# uCopter.net
KiCad netlist of a schematic drawn in EAGLE
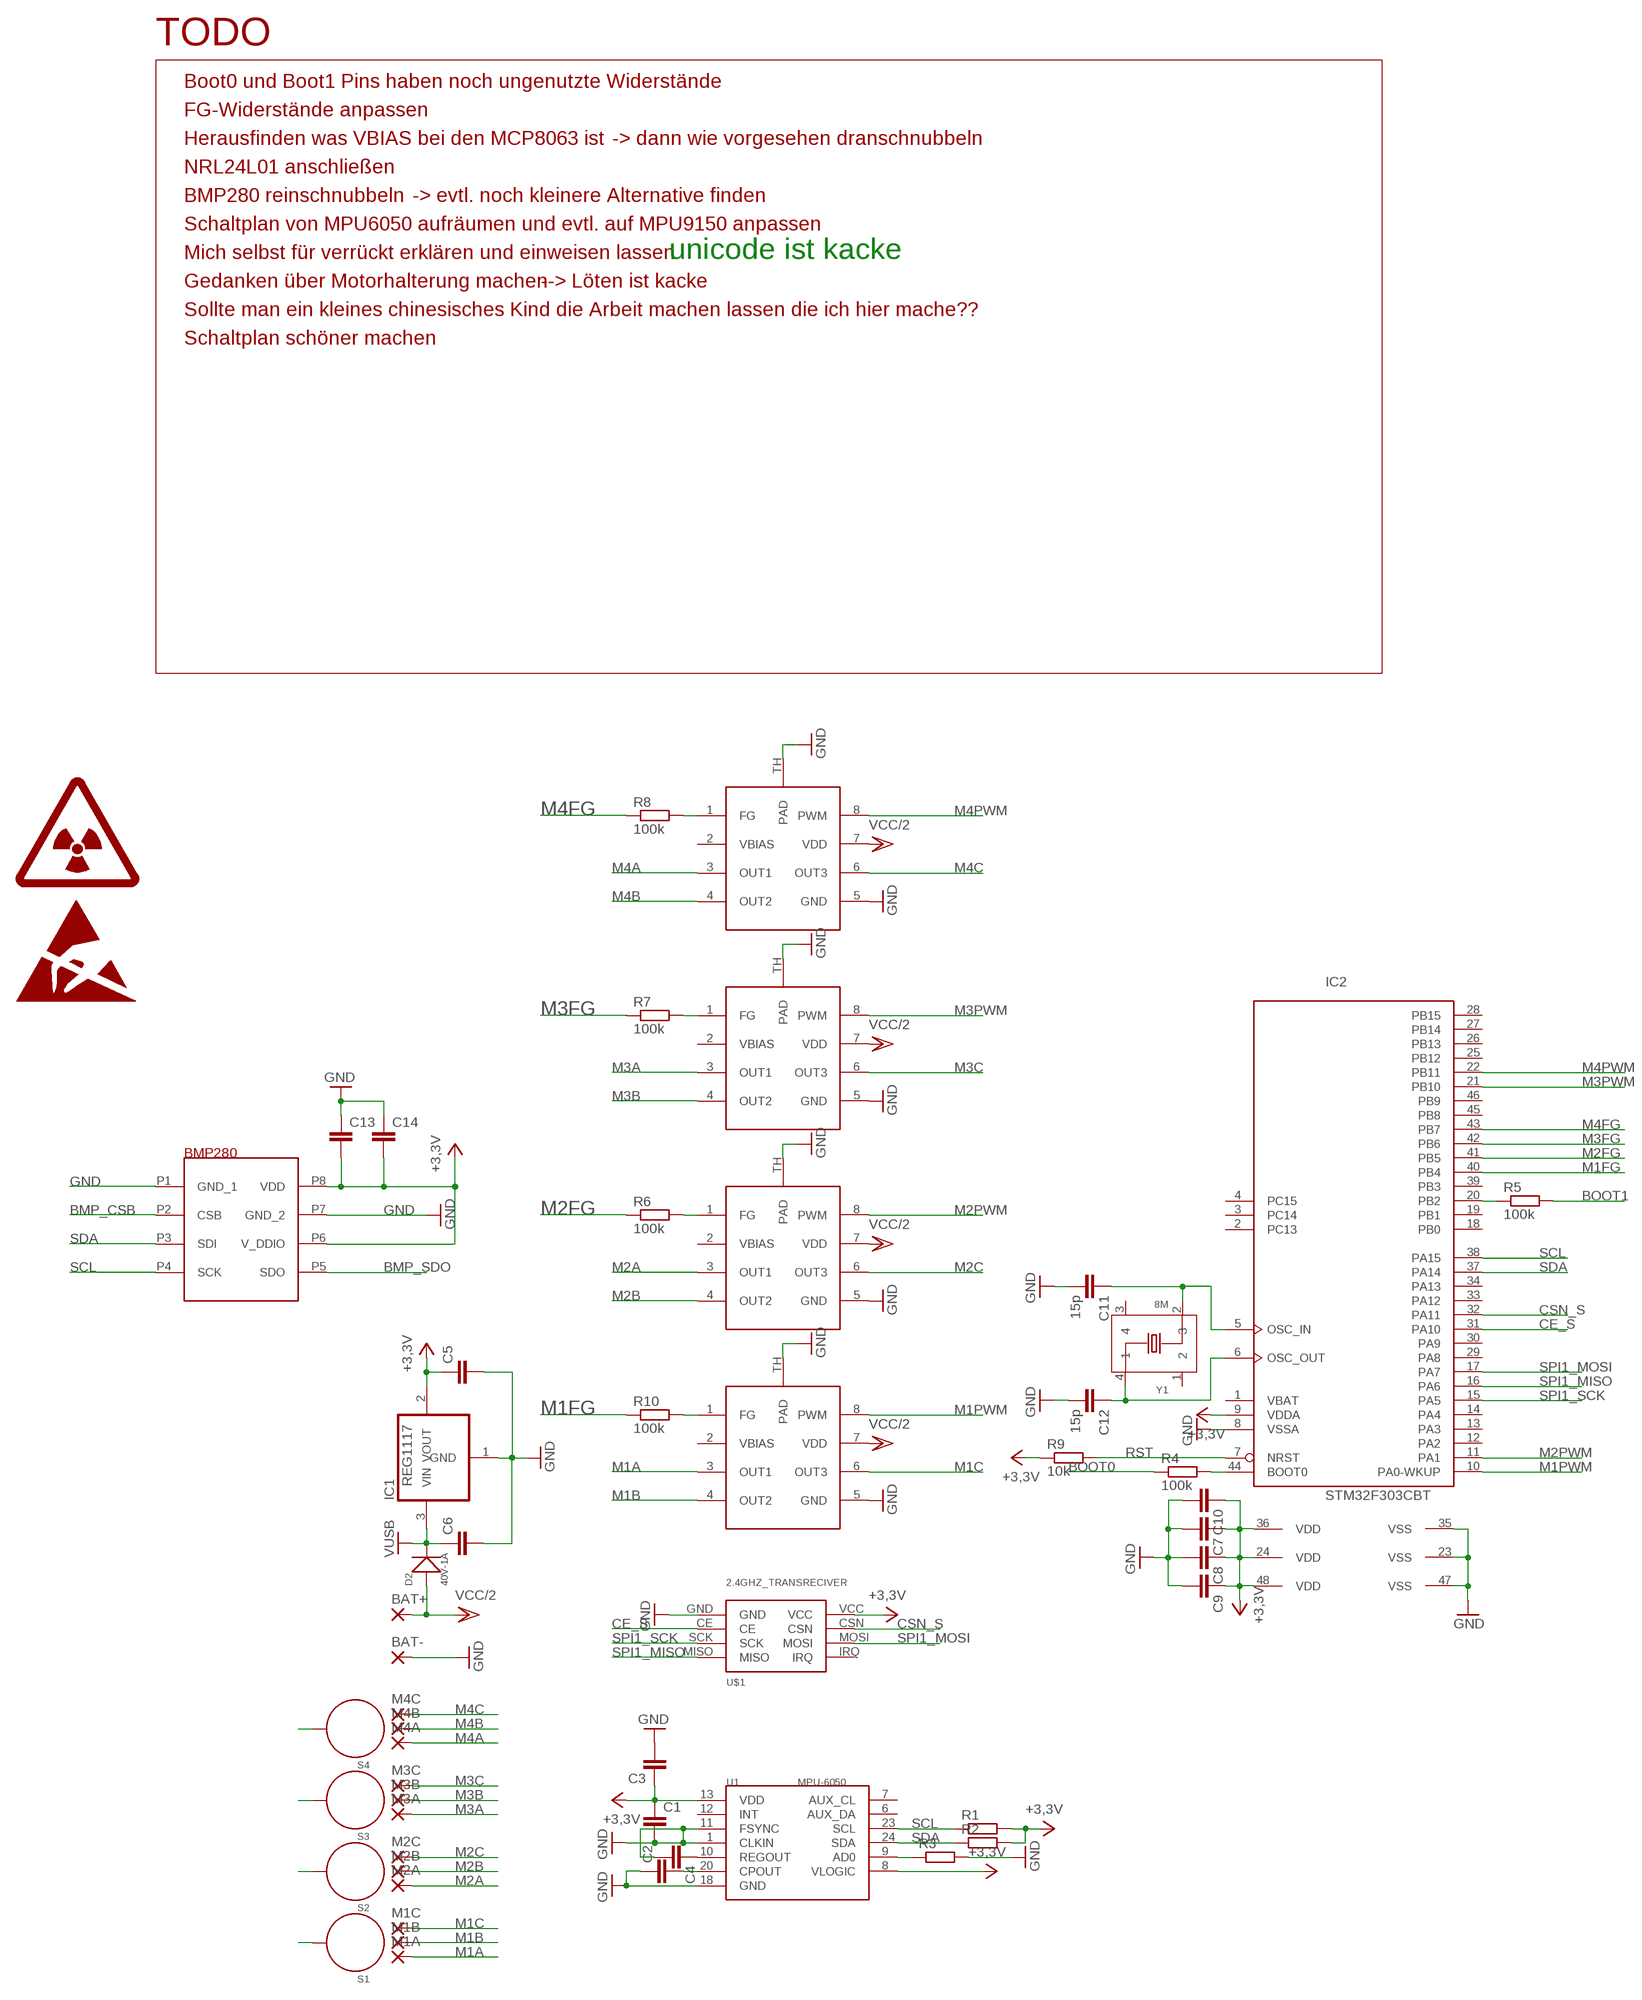
[diagram p0: schematic, sheet 1]

(export (version "E")
  (design (tool "Eeschema 10.0.6"))
  (components
    (comp (ref "BAT+")
      (value "SMD2")
      (footprint "eagle-import:SMD1,27-2,54")
      (libsource (lib "eagle-import") (part "SMD2"))
    )
    (comp (ref "BAT-")
      (value "SMD2")
      (footprint "eagle-import:SMD1,27-2,54")
      (libsource (lib "eagle-import") (part "SMD2"))
    )
    (comp (ref "C1")
      (value "C-EUC0402")
      (footprint "eagle-import:C0402")
      (libsource (lib "eagle-import") (part "C-EUC0402"))
    )
    (comp (ref "C2")
      (value "C-EUC0402")
      (footprint "eagle-import:C0402")
      (libsource (lib "eagle-import") (part "C-EUC0402"))
    )
    (comp (ref "C3")
      (value "C-EUC0402")
      (footprint "eagle-import:C0402")
      (libsource (lib "eagle-import") (part "C-EUC0402"))
    )
    (comp (ref "C4")
      (value "C-EUC0402")
      (footprint "eagle-import:C0402")
      (libsource (lib "eagle-import") (part "C-EUC0402"))
    )
    (comp (ref "C5")
      (value "C-EUC0603")
      (footprint "eagle-import:C0603")
      (libsource (lib "eagle-import") (part "C-EUC0603"))
    )
    (comp (ref "C6")
      (value "C-EUC0603")
      (footprint "eagle-import:C0603")
      (libsource (lib "eagle-import") (part "C-EUC0603"))
    )
    (comp (ref "C7")
      (value "C-EUC0402")
      (footprint "eagle-import:C0402")
      (libsource (lib "eagle-import") (part "C-EUC0402"))
    )
    (comp (ref "C8")
      (value "C-EUC0402")
      (footprint "eagle-import:C0402")
      (libsource (lib "eagle-import") (part "C-EUC0402"))
    )
    (comp (ref "C9")
      (value "C-EUC0402")
      (footprint "eagle-import:C0402")
      (libsource (lib "eagle-import") (part "C-EUC0402"))
    )
    (comp (ref "C10")
      (value "C-EUC0402")
      (footprint "eagle-import:C0402")
      (libsource (lib "eagle-import") (part "C-EUC0402"))
    )
    (comp (ref "C11")
      (value "15p")
      (footprint "eagle-import:C0402")
      (libsource (lib "eagle-import") (part "C-EUC0402"))
    )
    (comp (ref "C12")
      (value "15p")
      (footprint "eagle-import:C0402")
      (libsource (lib "eagle-import") (part "C-EUC0402"))
    )
    (comp (ref "C13")
      (value "C-EUC0402")
      (footprint "eagle-import:C0402")
      (libsource (lib "eagle-import") (part "C-EUC0402"))
    )
    (comp (ref "C14")
      (value "C-EUC0402")
      (footprint "eagle-import:C0402")
      (libsource (lib "eagle-import") (part "C-EUC0402"))
    )
    (comp (ref "D2")
      (value "40V-1A")
      (footprint "eagle-import:DO-214AC")
      (fields (field (name "MPN") "1N5819"))
      (libsource (lib "eagle-import") (part "SMD-DIODE-SCHOTTKY-40V-1A(DO-214AC)"))
    )
    (comp (ref "IC1")
      (value "REG1117")
      (footprint "eagle-import:SOT223")
      (libsource (lib "eagle-import") (part "REG1117"))
    )
    (comp (ref "IC2")
      (value "STM32F303CBT")
      (footprint "eagle-import:LQFP48")
      (libsource (lib "eagle-import") (part "STM32F303CTB"))
    )
    (comp (ref "M1A")
      (value "2,15/1,0")
      (footprint "eagle-import:2,15_1,0")
      (libsource (lib "eagle-import") (part "2,15/1,0"))
    )
    (comp (ref "M1B")
      (value "2,15/1,0")
      (footprint "eagle-import:2,15_1,0")
      (libsource (lib "eagle-import") (part "2,15/1,0"))
    )
    (comp (ref "M1C")
      (value "2,15/1,0")
      (footprint "eagle-import:2,15_1,0")
      (libsource (lib "eagle-import") (part "2,15/1,0"))
    )
    (comp (ref "M2A")
      (value "2,15/1,0")
      (footprint "eagle-import:2,15_1,0")
      (libsource (lib "eagle-import") (part "2,15/1,0"))
    )
    (comp (ref "M2B")
      (value "2,15/1,0")
      (footprint "eagle-import:2,15_1,0")
      (libsource (lib "eagle-import") (part "2,15/1,0"))
    )
    (comp (ref "M2C")
      (value "2,15/1,0")
      (footprint "eagle-import:2,15_1,0")
      (libsource (lib "eagle-import") (part "2,15/1,0"))
    )
    (comp (ref "M3A")
      (value "2,15/1,0")
      (footprint "eagle-import:2,15_1,0")
      (libsource (lib "eagle-import") (part "2,15/1,0"))
    )
    (comp (ref "M3B")
      (value "2,15/1,0")
      (footprint "eagle-import:2,15_1,0")
      (libsource (lib "eagle-import") (part "2,15/1,0"))
    )
    (comp (ref "M3C")
      (value "2,15/1,0")
      (footprint "eagle-import:2,15_1,0")
      (libsource (lib "eagle-import") (part "2,15/1,0"))
    )
    (comp (ref "M4A")
      (value "2,15/1,0")
      (footprint "eagle-import:2,15_1,0")
      (libsource (lib "eagle-import") (part "2,15/1,0"))
    )
    (comp (ref "M4B")
      (value "2,15/1,0")
      (footprint "eagle-import:2,15_1,0")
      (libsource (lib "eagle-import") (part "2,15/1,0"))
    )
    (comp (ref "M4C")
      (value "2,15/1,0")
      (footprint "eagle-import:2,15_1,0")
      (libsource (lib "eagle-import") (part "2,15/1,0"))
    )
    (comp (ref "R1")
      (value "R-EU_R0402")
      (footprint "eagle-import:R0402")
      (libsource (lib "eagle-import") (part "R-EU_R0402"))
    )
    (comp (ref "R2")
      (value "R-EU_R0402")
      (footprint "eagle-import:R0402")
      (libsource (lib "eagle-import") (part "R-EU_R0402"))
    )
    (comp (ref "R3")
      (value "R-EU_R0402")
      (footprint "eagle-import:R0402")
      (libsource (lib "eagle-import") (part "R-EU_R0402"))
    )
    (comp (ref "R4")
      (value "100k")
      (footprint "eagle-import:R0402")
      (libsource (lib "eagle-import") (part "R-EU_R0402"))
    )
    (comp (ref "R5")
      (value "100k")
      (footprint "eagle-import:R0402")
      (libsource (lib "eagle-import") (part "R-EU_R0402"))
    )
    (comp (ref "R6")
      (value "100k")
      (footprint "eagle-import:R0402")
      (libsource (lib "eagle-import") (part "R-EU_R0402"))
    )
    (comp (ref "R7")
      (value "100k")
      (footprint "eagle-import:R0402")
      (libsource (lib "eagle-import") (part "R-EU_R0402"))
    )
    (comp (ref "R8")
      (value "100k")
      (footprint "eagle-import:R0402")
      (libsource (lib "eagle-import") (part "R-EU_R0402"))
    )
    (comp (ref "R9")
      (value "10k")
      (footprint "eagle-import:R0402")
      (libsource (lib "eagle-import") (part "R-EU_R0402"))
    )
    (comp (ref "R10")
      (value "100k")
      (footprint "eagle-import:R0402")
      (libsource (lib "eagle-import") (part "R-EU_R0402"))
    )
    (comp (ref "S1")
      (value "STANDOFF_ELECTRICAL")
      (footprint "eagle-import:STANDOFF-ELECTRICAL")
      (libsource (lib "eagle-import") (part "STANDOFF_ELECTRICAL"))
    )
    (comp (ref "S2")
      (value "STANDOFF_ELECTRICAL")
      (footprint "eagle-import:STANDOFF-ELECTRICAL")
      (libsource (lib "eagle-import") (part "STANDOFF_ELECTRICAL"))
    )
    (comp (ref "S3")
      (value "STANDOFF_ELECTRICAL")
      (footprint "eagle-import:STANDOFF-ELECTRICAL")
      (libsource (lib "eagle-import") (part "STANDOFF_ELECTRICAL"))
    )
    (comp (ref "S4")
      (value "STANDOFF_ELECTRICAL")
      (footprint "eagle-import:STANDOFF-ELECTRICAL")
      (libsource (lib "eagle-import") (part "STANDOFF_ELECTRICAL"))
    )
    (comp (ref "T1")
      (value "BMP280")
      (footprint "eagle-import:BMP280")
      (libsource (lib "eagle-import") (part "BMP280"))
    )
    (comp (ref "U$1")
      (value "2.4GHZ_TRANSRECIVER")
      (footprint "eagle-import:2.4GHZ_TRANSRECIVER")
      (libsource (lib "eagle-import") (part "2.4GHZ_TRANSRECIVER"))
    )
    (comp (ref "U$6")
      (value "MCP8063")
      (footprint "eagle-import:DFN8-4X4")
      (libsource (lib "eagle-import") (part "MCP8063"))
    )
    (comp (ref "U$7")
      (value "MCP8063")
      (footprint "eagle-import:DFN8-4X4")
      (libsource (lib "eagle-import") (part "MCP8063"))
    )
    (comp (ref "U$8")
      (value "MCP8063")
      (footprint "eagle-import:DFN8-4X4")
      (libsource (lib "eagle-import") (part "MCP8063"))
    )
    (comp (ref "U$9")
      (value "MCP8063")
      (footprint "eagle-import:DFN8-4X4")
      (libsource (lib "eagle-import") (part "MCP8063"))
    )
    (comp (ref "U1")
      (value "MPU-6050")
      (footprint "eagle-import:QFN24G-0.5-4X4MM")
      (libsource (lib "eagle-import") (part "MOTION/POSITION-MPU-6050(QFN24)"))
    )
    (comp (ref "Y1")
      (value "8M")
      (footprint "eagle-import:X4-SMD-3.2X2.5X0.7MM")
      (fields (field (name "MPN") "7M-27.120MAAJ-T"))
      (libsource (lib "eagle-import") (part "SMD-CRYSTAL-27.12MHZ-18PF-30PPM-60R(4P-3.2X2.5MM)"))
    )
  )
  (nets
    (net (code "1") (name "+3,3V") (class "Default")
      (node (ref "C1") (pin "1") (pinfunction "1_1") (pintype "passive"))
      (node (ref "C10") (pin "1") (pinfunction "1_1") (pintype "passive"))
      (node (ref "C13") (pin "2") (pinfunction "2_2") (pintype "passive"))
      (node (ref "C14") (pin "2") (pinfunction "2_2") (pintype "passive"))
      (node (ref "C3") (pin "1") (pinfunction "1_1") (pintype "passive"))
      (node (ref "C5") (pin "1") (pinfunction "1_1") (pintype "passive"))
      (node (ref "C7") (pin "1") (pinfunction "1_1") (pintype "passive"))
      (node (ref "C8") (pin "1") (pinfunction "1_1") (pintype "passive"))
      (node (ref "C9") (pin "1") (pinfunction "1_1") (pintype "passive"))
      (node (ref "IC1") (pin "2") (pinfunction "VOUT_2") (pintype "output"))
      (node (ref "IC2") (pin "24") (pinfunction "VDD_24") (pintype "power_in"))
      (node (ref "IC2") (pin "36") (pinfunction "VDD_36") (pintype "power_in"))
      (node (ref "IC2") (pin "48") (pinfunction "VDD_48") (pintype "power_in"))
      (node (ref "IC2") (pin "9") (pinfunction "VDDA_9") (pintype "power_in"))
      (node (ref "R1") (pin "2") (pinfunction "2_2") (pintype "passive"))
      (node (ref "R2") (pin "2") (pinfunction "2_2") (pintype "passive"))
      (node (ref "R9") (pin "1") (pinfunction "1_1") (pintype "passive"))
      (node (ref "T1") (pin "P6") (pinfunction "V_DDIO_P6") (pintype "bidirectional"))
      (node (ref "T1") (pin "P8") (pinfunction "VDD_P8") (pintype "power_in"))
      (node (ref "U$1") (pin "VCC") (pinfunction "VCC_VCC") (pintype "bidirectional"))
      (node (ref "U1") (pin "13") (pinfunction "VDD_13") (pintype "bidirectional"))
      (node (ref "U1") (pin "8") (pinfunction "VLOGIC_8") (pintype "bidirectional"))
    )
    (net (code "2") (name "/BMP_CSB") (class "Default")
      (node (ref "T1") (pin "P2") (pinfunction "CSB_P2") (pintype "bidirectional"))
    )
    (net (code "3") (name "/BMP_SDO") (class "Default")
      (node (ref "T1") (pin "P5") (pinfunction "SDO_P5") (pintype "bidirectional"))
    )
    (net (code "4") (name "/BOOT0") (class "Default")
      (node (ref "R4") (pin "1") (pinfunction "1_1") (pintype "passive"))
    )
    (net (code "5") (name "/BOOT1") (class "Default")
      (node (ref "R5") (pin "2") (pinfunction "2_2") (pintype "passive"))
    )
    (net (code "6") (name "/CE_S") (class "Default")
      (node (ref "IC2") (pin "31") (pinfunction "PA10_31") (pintype "bidirectional"))
      (node (ref "U$1") (pin "CE") (pinfunction "CE_CE") (pintype "bidirectional"))
    )
    (net (code "7") (name "/CSN_S") (class "Default")
      (node (ref "IC2") (pin "32") (pinfunction "PA11_32") (pintype "bidirectional"))
      (node (ref "U$1") (pin "CSN") (pinfunction "CSN_CSN") (pintype "bidirectional"))
    )
    (net (code "8") (name "/M1A") (class "Default")
      (node (ref "M1A") (pin "1") (pinfunction "P_1") (pintype "passive"))
      (node (ref "U$6") (pin "3") (pinfunction "OUT1_3") (pintype "bidirectional"))
    )
    (net (code "9") (name "/M1B") (class "Default")
      (node (ref "M1B") (pin "1") (pinfunction "P_1") (pintype "passive"))
      (node (ref "U$6") (pin "4") (pinfunction "OUT2_4") (pintype "bidirectional"))
    )
    (net (code "10") (name "/M1C") (class "Default")
      (node (ref "M1C") (pin "1") (pinfunction "P_1") (pintype "passive"))
      (node (ref "U$6") (pin "6") (pinfunction "OUT3_6") (pintype "bidirectional"))
    )
    (net (code "11") (name "/M1FG") (class "Default")
      (node (ref "IC2") (pin "40") (pinfunction "PB4_40") (pintype "bidirectional"))
      (node (ref "R10") (pin "1") (pinfunction "1_1") (pintype "passive"))
    )
    (net (code "12") (name "/M1PWM") (class "Default")
      (node (ref "IC2") (pin "10") (pinfunction "PA0-WKUP_10") (pintype "bidirectional"))
      (node (ref "U$6") (pin "8") (pinfunction "PWM_8") (pintype "bidirectional"))
    )
    (net (code "13") (name "/M2A") (class "Default")
      (node (ref "M2A") (pin "1") (pinfunction "P_1") (pintype "passive"))
      (node (ref "U$7") (pin "3") (pinfunction "OUT1_3") (pintype "bidirectional"))
    )
    (net (code "14") (name "/M2B") (class "Default")
      (node (ref "M2B") (pin "1") (pinfunction "P_1") (pintype "passive"))
      (node (ref "U$7") (pin "4") (pinfunction "OUT2_4") (pintype "bidirectional"))
    )
    (net (code "15") (name "/M2C") (class "Default")
      (node (ref "M2C") (pin "1") (pinfunction "P_1") (pintype "passive"))
      (node (ref "U$7") (pin "6") (pinfunction "OUT3_6") (pintype "bidirectional"))
    )
    (net (code "16") (name "/M2FG") (class "Default")
      (node (ref "IC2") (pin "41") (pinfunction "PB5_41") (pintype "bidirectional"))
      (node (ref "R6") (pin "1") (pinfunction "1_1") (pintype "passive"))
    )
    (net (code "17") (name "/M2PWM") (class "Default")
      (node (ref "IC2") (pin "11") (pinfunction "PA1_11") (pintype "bidirectional"))
      (node (ref "U$7") (pin "8") (pinfunction "PWM_8") (pintype "bidirectional"))
    )
    (net (code "18") (name "/M3A") (class "Default")
      (node (ref "M3A") (pin "1") (pinfunction "P_1") (pintype "passive"))
      (node (ref "U$8") (pin "3") (pinfunction "OUT1_3") (pintype "bidirectional"))
    )
    (net (code "19") (name "/M3B") (class "Default")
      (node (ref "M3B") (pin "1") (pinfunction "P_1") (pintype "passive"))
      (node (ref "U$8") (pin "4") (pinfunction "OUT2_4") (pintype "bidirectional"))
    )
    (net (code "20") (name "/M3C") (class "Default")
      (node (ref "M3C") (pin "1") (pinfunction "P_1") (pintype "passive"))
      (node (ref "U$8") (pin "6") (pinfunction "OUT3_6") (pintype "bidirectional"))
    )
    (net (code "21") (name "/M3FG") (class "Default")
      (node (ref "IC2") (pin "42") (pinfunction "PB6_42") (pintype "bidirectional"))
      (node (ref "R7") (pin "1") (pinfunction "1_1") (pintype "passive"))
    )
    (net (code "22") (name "/M3PWM") (class "Default")
      (node (ref "IC2") (pin "21") (pinfunction "PB10_21") (pintype "bidirectional"))
      (node (ref "U$8") (pin "8") (pinfunction "PWM_8") (pintype "bidirectional"))
    )
    (net (code "23") (name "/M4A") (class "Default")
      (node (ref "M4A") (pin "1") (pinfunction "P_1") (pintype "passive"))
      (node (ref "U$9") (pin "3") (pinfunction "OUT1_3") (pintype "bidirectional"))
    )
    (net (code "24") (name "/M4B") (class "Default")
      (node (ref "M4B") (pin "1") (pinfunction "P_1") (pintype "passive"))
      (node (ref "U$9") (pin "4") (pinfunction "OUT2_4") (pintype "bidirectional"))
    )
    (net (code "25") (name "/M4C") (class "Default")
      (node (ref "M4C") (pin "1") (pinfunction "P_1") (pintype "passive"))
      (node (ref "U$9") (pin "6") (pinfunction "OUT3_6") (pintype "bidirectional"))
    )
    (net (code "26") (name "/M4FG") (class "Default")
      (node (ref "IC2") (pin "43") (pinfunction "PB7_43") (pintype "bidirectional"))
      (node (ref "R8") (pin "1") (pinfunction "1_1") (pintype "passive"))
    )
    (net (code "27") (name "/M4PWM") (class "Default")
      (node (ref "IC2") (pin "22") (pinfunction "PB11_22") (pintype "bidirectional"))
      (node (ref "U$9") (pin "8") (pinfunction "PWM_8") (pintype "bidirectional"))
    )
    (net (code "28") (name "/RST") (class "Default")
      (node (ref "IC2") (pin "7") (pinfunction "NRST_7") (pintype "bidirectional"))
      (node (ref "R9") (pin "2") (pinfunction "2_2") (pintype "passive"))
    )
    (net (code "29") (name "/SCL") (class "Default")
      (node (ref "IC2") (pin "38") (pinfunction "PA15_38") (pintype "bidirectional"))
      (node (ref "R1") (pin "1") (pinfunction "1_1") (pintype "passive"))
      (node (ref "T1") (pin "P4") (pinfunction "SCK_P4") (pintype "bidirectional"))
      (node (ref "U1") (pin "23") (pinfunction "SCL_23") (pintype "bidirectional"))
    )
    (net (code "30") (name "/SDA") (class "Default")
      (node (ref "IC2") (pin "37") (pinfunction "PA14_37") (pintype "bidirectional"))
      (node (ref "R2") (pin "1") (pinfunction "1_1") (pintype "passive"))
      (node (ref "T1") (pin "P3") (pinfunction "SDI_P3") (pintype "bidirectional"))
      (node (ref "U1") (pin "24") (pinfunction "SDA_24") (pintype "bidirectional"))
    )
    (net (code "31") (name "/SPI1_MISO") (class "Default")
      (node (ref "IC2") (pin "16") (pinfunction "PA6_16") (pintype "bidirectional"))
      (node (ref "U$1") (pin "MISO") (pinfunction "MISO_MISO") (pintype "bidirectional"))
    )
    (net (code "32") (name "/SPI1_MOSI") (class "Default")
      (node (ref "IC2") (pin "17") (pinfunction "PA7_17") (pintype "bidirectional"))
      (node (ref "U$1") (pin "MOSI") (pinfunction "MOSI_MOSI") (pintype "bidirectional"))
    )
    (net (code "33") (name "/SPI1_SCK") (class "Default")
      (node (ref "IC2") (pin "15") (pinfunction "PA5_15") (pintype "bidirectional"))
      (node (ref "U$1") (pin "SCK") (pinfunction "SCK_SCK") (pintype "bidirectional"))
    )
    (net (code "34") (name "/VBAT") (class "Default")
      (node (ref "IC2") (pin "1") (pinfunction "VBAT_1") (pintype "power_in"))
    )
    (net (code "35") (name "GND") (class "Default")
      (node (ref "BAT-") (pin "1") (pinfunction "P_1") (pintype "passive"))
      (node (ref "C1") (pin "2") (pinfunction "2_2") (pintype "passive"))
      (node (ref "C10") (pin "2") (pinfunction "2_2") (pintype "passive"))
      (node (ref "C11") (pin "2") (pinfunction "2_2") (pintype "passive"))
      (node (ref "C12") (pin "2") (pinfunction "2_2") (pintype "passive"))
      (node (ref "C13") (pin "1") (pinfunction "1_1") (pintype "passive"))
      (node (ref "C14") (pin "1") (pinfunction "1_1") (pintype "passive"))
      (node (ref "C2") (pin "1") (pinfunction "1_1") (pintype "passive"))
      (node (ref "C3") (pin "2") (pinfunction "2_2") (pintype "passive"))
      (node (ref "C4") (pin "2") (pinfunction "2_2") (pintype "passive"))
      (node (ref "C5") (pin "2") (pinfunction "2_2") (pintype "passive"))
      (node (ref "C6") (pin "2") (pinfunction "2_2") (pintype "passive"))
      (node (ref "C7") (pin "2") (pinfunction "2_2") (pintype "passive"))
      (node (ref "C8") (pin "2") (pinfunction "2_2") (pintype "passive"))
      (node (ref "C9") (pin "2") (pinfunction "2_2") (pintype "passive"))
      (node (ref "IC1") (pin "1") (pinfunction "GND_1") (pintype "power_in"))
      (node (ref "IC2") (pin "23") (pinfunction "VSS_23") (pintype "power_in"))
      (node (ref "IC2") (pin "35") (pinfunction "VSS_35") (pintype "power_in"))
      (node (ref "IC2") (pin "47") (pinfunction "VSS_47") (pintype "power_in"))
      (node (ref "IC2") (pin "8") (pinfunction "VSSA_8") (pintype "power_in"))
      (node (ref "R3") (pin "2") (pinfunction "2_2") (pintype "passive"))
      (node (ref "T1") (pin "P1") (pinfunction "GND_1_P1") (pintype "power_in"))
      (node (ref "T1") (pin "P7") (pinfunction "GND_2_P7") (pintype "power_in"))
      (node (ref "U$1") (pin "GND") (pinfunction "GND_GND") (pintype "bidirectional"))
      (node (ref "U$6") (pin "5") (pinfunction "GND_5") (pintype "bidirectional"))
      (node (ref "U$6") (pin "TH") (pinfunction "PAD_TH") (pintype "bidirectional"))
      (node (ref "U$7") (pin "5") (pinfunction "GND_5") (pintype "bidirectional"))
      (node (ref "U$7") (pin "TH") (pinfunction "PAD_TH") (pintype "bidirectional"))
      (node (ref "U$8") (pin "5") (pinfunction "GND_5") (pintype "bidirectional"))
      (node (ref "U$8") (pin "TH") (pinfunction "PAD_TH") (pintype "bidirectional"))
      (node (ref "U$9") (pin "5") (pinfunction "GND_5") (pintype "bidirectional"))
      (node (ref "U$9") (pin "TH") (pinfunction "PAD_TH") (pintype "bidirectional"))
      (node (ref "U1") (pin "1") (pinfunction "CLKIN_1") (pintype "bidirectional"))
      (node (ref "U1") (pin "11") (pinfunction "FSYNC_11") (pintype "bidirectional"))
      (node (ref "U1") (pin "18") (pinfunction "GND_18") (pintype "bidirectional"))
    )
    (net (code "36") (name "Net-(IC2A-BOOT0)") (class "Default")
      (node (ref "IC2") (pin "44") (pinfunction "BOOT0_44") (pintype "input"))
      (node (ref "R4") (pin "2") (pinfunction "2_2") (pintype "passive"))
    )
    (net (code "37") (name "Net-(IC2A-OSC_IN)") (class "Default")
      (node (ref "C11") (pin "1") (pinfunction "1_1") (pintype "passive"))
      (node (ref "IC2") (pin "5") (pinfunction "OSC_IN_5") (pintype "bidirectional"))
      (node (ref "Y1") (pin "2") (pinfunction "3_2") (pintype "bidirectional"))
    )
    (net (code "38") (name "Net-(IC2A-OSC_OUT)") (class "Default")
      (node (ref "C12") (pin "1") (pinfunction "1_1") (pintype "passive"))
      (node (ref "IC2") (pin "6") (pinfunction "OSC_OUT_6") (pintype "bidirectional"))
      (node (ref "Y1") (pin "4") (pinfunction "1_4") (pintype "bidirectional"))
    )
    (net (code "39") (name "Net-(IC2A-PB2)") (class "Default")
      (node (ref "IC2") (pin "20") (pinfunction "PB2_20") (pintype "bidirectional"))
      (node (ref "R5") (pin "1") (pinfunction "1_1") (pintype "passive"))
    )
    (net (code "40") (name "Net-(U$6-FG)") (class "Default")
      (node (ref "R10") (pin "2") (pinfunction "2_2") (pintype "passive"))
      (node (ref "U$6") (pin "1") (pinfunction "FG_1") (pintype "bidirectional"))
    )
    (net (code "41") (name "Net-(U$7-FG)") (class "Default")
      (node (ref "R6") (pin "2") (pinfunction "2_2") (pintype "passive"))
      (node (ref "U$7") (pin "1") (pinfunction "FG_1") (pintype "bidirectional"))
    )
    (net (code "42") (name "Net-(U$8-FG)") (class "Default")
      (node (ref "R7") (pin "2") (pinfunction "2_2") (pintype "passive"))
      (node (ref "U$8") (pin "1") (pinfunction "FG_1") (pintype "bidirectional"))
    )
    (net (code "43") (name "Net-(U$9-FG)") (class "Default")
      (node (ref "R8") (pin "2") (pinfunction "2_2") (pintype "passive"))
      (node (ref "U$9") (pin "1") (pinfunction "FG_1") (pintype "bidirectional"))
    )
    (net (code "44") (name "Net-(U1-AD0)") (class "Default")
      (node (ref "R3") (pin "1") (pinfunction "1_1") (pintype "passive"))
      (node (ref "U1") (pin "9") (pinfunction "AD0_9") (pintype "bidirectional"))
    )
    (net (code "45") (name "Net-(U1-CPOUT)") (class "Default")
      (node (ref "C2") (pin "2") (pinfunction "2_2") (pintype "passive"))
      (node (ref "U1") (pin "20") (pinfunction "CPOUT_20") (pintype "bidirectional"))
    )
    (net (code "46") (name "Net-(U1-REGOUT)") (class "Default")
      (node (ref "C4") (pin "1") (pinfunction "1_1") (pintype "passive"))
      (node (ref "U1") (pin "10") (pinfunction "REGOUT_10") (pintype "bidirectional"))
    )
    (net (code "47") (name "VCC{slash}2") (class "Default")
      (node (ref "BAT+") (pin "1") (pinfunction "P_1") (pintype "passive"))
      (node (ref "D2") (pin "1") (pinfunction "+_1") (pintype "passive"))
      (node (ref "U$6") (pin "7") (pinfunction "VDD_7") (pintype "bidirectional"))
      (node (ref "U$7") (pin "7") (pinfunction "VDD_7") (pintype "bidirectional"))
      (node (ref "U$8") (pin "7") (pinfunction "VDD_7") (pintype "bidirectional"))
      (node (ref "U$9") (pin "7") (pinfunction "VDD_7") (pintype "bidirectional"))
    )
    (net (code "48") (name "VUSB") (class "Default")
      (node (ref "C6") (pin "1") (pinfunction "1_1") (pintype "passive"))
      (node (ref "D2") (pin "2") (pinfunction "-_2") (pintype "passive"))
      (node (ref "IC1") (pin "3") (pinfunction "VIN_3") (pintype "input"))
    )
    (net (code "49") (name "unconnected-(IC2A-PA2-Pad12)") (class "Default")
      (node (ref "IC2") (pin "12") (pinfunction "PA2_12") (pintype "bidirectional"))
    )
    (net (code "50") (name "unconnected-(IC2A-PA3-Pad13)") (class "Default")
      (node (ref "IC2") (pin "13") (pinfunction "PA3_13") (pintype "bidirectional"))
    )
    (net (code "51") (name "unconnected-(IC2A-PA4-Pad14)") (class "Default")
      (node (ref "IC2") (pin "14") (pinfunction "PA4_14") (pintype "bidirectional"))
    )
    (net (code "52") (name "unconnected-(IC2A-PA8-Pad29)") (class "Default")
      (node (ref "IC2") (pin "29") (pinfunction "PA8_29") (pintype "bidirectional"))
    )
    (net (code "53") (name "unconnected-(IC2A-PA9-Pad30)") (class "Default")
      (node (ref "IC2") (pin "30") (pinfunction "PA9_30") (pintype "bidirectional"))
    )
    (net (code "54") (name "unconnected-(IC2A-PA12-Pad33)") (class "Default")
      (node (ref "IC2") (pin "33") (pinfunction "PA12_33") (pintype "bidirectional"))
    )
    (net (code "55") (name "unconnected-(IC2A-PA13-Pad34)") (class "Default")
      (node (ref "IC2") (pin "34") (pinfunction "PA13_34") (pintype "bidirectional"))
    )
    (net (code "56") (name "unconnected-(IC2A-PB0-Pad18)") (class "Default")
      (node (ref "IC2") (pin "18") (pinfunction "PB0_18") (pintype "bidirectional"))
    )
    (net (code "57") (name "unconnected-(IC2A-PB1-Pad19)") (class "Default")
      (node (ref "IC2") (pin "19") (pinfunction "PB1_19") (pintype "bidirectional"))
    )
    (net (code "58") (name "unconnected-(IC2A-PB3-Pad39)") (class "Default")
      (node (ref "IC2") (pin "39") (pinfunction "PB3_39") (pintype "bidirectional"))
    )
    (net (code "59") (name "unconnected-(IC2A-PB8-Pad45)") (class "Default")
      (node (ref "IC2") (pin "45") (pinfunction "PB8_45") (pintype "bidirectional"))
    )
    (net (code "60") (name "unconnected-(IC2A-PB9-Pad46)") (class "Default")
      (node (ref "IC2") (pin "46") (pinfunction "PB9_46") (pintype "bidirectional"))
    )
    (net (code "61") (name "unconnected-(IC2A-PB12-Pad25)") (class "Default")
      (node (ref "IC2") (pin "25") (pinfunction "PB12_25") (pintype "bidirectional"))
    )
    (net (code "62") (name "unconnected-(IC2A-PB13-Pad26)") (class "Default")
      (node (ref "IC2") (pin "26") (pinfunction "PB13_26") (pintype "bidirectional"))
    )
    (net (code "63") (name "unconnected-(IC2A-PB14-Pad27)") (class "Default")
      (node (ref "IC2") (pin "27") (pinfunction "PB14_27") (pintype "bidirectional"))
    )
    (net (code "64") (name "unconnected-(IC2A-PB15-Pad28)") (class "Default")
      (node (ref "IC2") (pin "28") (pinfunction "PB15_28") (pintype "bidirectional"))
    )
    (net (code "65") (name "unconnected-(IC2A-PC13-Pad2)") (class "Default")
      (node (ref "IC2") (pin "2") (pinfunction "PC13_2") (pintype "bidirectional"))
    )
    (net (code "66") (name "unconnected-(IC2A-PC14-Pad3)") (class "Default")
      (node (ref "IC2") (pin "3") (pinfunction "PC14_3") (pintype "bidirectional"))
    )
    (net (code "67") (name "unconnected-(IC2A-PC15-Pad4)") (class "Default")
      (node (ref "IC2") (pin "4") (pinfunction "PC15_4") (pintype "bidirectional"))
    )
    (net (code "68") (name "unconnected-(S1-P$1-PadP1)") (class "Default")
      (node (ref "S1") (pin "P1") (pinfunction "P$1_P1") (pintype "bidirectional"))
    )
    (net (code "69") (name "unconnected-(S2-P$1-PadP1)") (class "Default")
      (node (ref "S2") (pin "P1") (pinfunction "P$1_P1") (pintype "bidirectional"))
    )
    (net (code "70") (name "unconnected-(S3-P$1-PadP1)") (class "Default")
      (node (ref "S3") (pin "P1") (pinfunction "P$1_P1") (pintype "bidirectional"))
    )
    (net (code "71") (name "unconnected-(S4-P$1-PadP1)") (class "Default")
      (node (ref "S4") (pin "P1") (pinfunction "P$1_P1") (pintype "bidirectional"))
    )
    (net (code "72") (name "unconnected-(U$1-PadIRQ)") (class "Default")
      (node (ref "U$1") (pin "IRQ") (pinfunction "IRQ_IRQ") (pintype "bidirectional"))
    )
    (net (code "73") (name "unconnected-(U$6-VBIAS-Pad2)") (class "Default")
      (node (ref "U$6") (pin "2") (pinfunction "VBIAS_2") (pintype "bidirectional"))
    )
    (net (code "74") (name "unconnected-(U$7-VBIAS-Pad2)") (class "Default")
      (node (ref "U$7") (pin "2") (pinfunction "VBIAS_2") (pintype "bidirectional"))
    )
    (net (code "75") (name "unconnected-(U$8-VBIAS-Pad2)") (class "Default")
      (node (ref "U$8") (pin "2") (pinfunction "VBIAS_2") (pintype "bidirectional"))
    )
    (net (code "76") (name "unconnected-(U$9-VBIAS-Pad2)") (class "Default")
      (node (ref "U$9") (pin "2") (pinfunction "VBIAS_2") (pintype "bidirectional"))
    )
    (net (code "77") (name "unconnected-(U1-AUX_CL-Pad7)") (class "Default")
      (node (ref "U1") (pin "7") (pinfunction "AUX_CL_7") (pintype "bidirectional"))
    )
    (net (code "78") (name "unconnected-(U1-AUX_DA-Pad6)") (class "Default")
      (node (ref "U1") (pin "6") (pinfunction "AUX_DA_6") (pintype "bidirectional"))
    )
    (net (code "79") (name "unconnected-(U1-INT-Pad12)") (class "Default")
      (node (ref "U1") (pin "12") (pinfunction "INT_12") (pintype "bidirectional"))
    )
    (net (code "80") (name "unconnected-(Y1-2-Pad1)") (class "Default")
      (node (ref "Y1") (pin "1") (pinfunction "2_1") (pintype "bidirectional"))
    )
    (net (code "81") (name "unconnected-(Y1-4-Pad3)") (class "Default")
      (node (ref "Y1") (pin "3") (pinfunction "4_3") (pintype "bidirectional"))
    )
  )
)
